# ws2812B.net
KiCad netlist of a schematic drawn in EAGLE
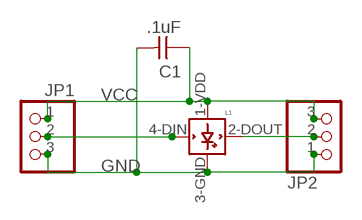
[diagram p0: schematic, sheet 1]

(export (version "E")
  (design (tool "Eeschema 10.0.6"))
  (components
    (comp (ref "C1")
      (value ".1uF")
      (footprint "eagle-import:C1206FAB")
      (libsource (lib "eagle-import") (part "CAP-UNPOLARIZEDFAB"))
    )
    (comp (ref "JP1")
      (value "PINHD-1X3CB")
      (footprint "eagle-import:1X03-CLEANBIG")
      (libsource (lib "eagle-import") (part "PINHD-1X3CB"))
    )
    (comp (ref "JP2")
      (value "PINHD-1X3CB")
      (footprint "eagle-import:1X03-CLEANBIG")
      (libsource (lib "eagle-import") (part "PINHD-1X3CB"))
    )
    (comp (ref "L1")
      (value "WS2812B")
      (footprint "eagle-import:WS2812B")
      (libsource (lib "eagle-import") (part "WS2812B"))
    )
  )
  (nets
    (net (code "1") (name "/GND") (class "Default")
      (node (ref "C1") (pin "2") (pinfunction "2_2") (pintype "passive"))
      (node (ref "JP1") (pin "3") (pinfunction "3_3") (pintype "passive"))
      (node (ref "JP2") (pin "1") (pinfunction "1_1") (pintype "passive"))
      (node (ref "L1") (pin "3-GND") (pinfunction "GND_3-GND") (pintype "bidirectional"))
    )
    (net (code "2") (name "/VCC") (class "Default")
      (node (ref "C1") (pin "1") (pinfunction "1_1") (pintype "passive"))
      (node (ref "JP1") (pin "1") (pinfunction "1_1") (pintype "passive"))
      (node (ref "JP2") (pin "3") (pinfunction "3_3") (pintype "passive"))
      (node (ref "L1") (pin "1-VDD") (pinfunction "VDD_1-VDD") (pintype "bidirectional"))
    )
    (net (code "3") (name "Net-(L1-DIN)") (class "Default")
      (node (ref "JP1") (pin "2") (pinfunction "2_2") (pintype "passive"))
      (node (ref "L1") (pin "4-DIN") (pinfunction "DIN_4-DIN") (pintype "input"))
    )
    (net (code "4") (name "Net-(L1-DOUT)") (class "Default")
      (node (ref "JP2") (pin "2") (pinfunction "2_2") (pintype "passive"))
      (node (ref "L1") (pin "2-DOUT") (pinfunction "DOUT_2-DOUT") (pintype "output"))
    )
  )
)
